# ServoConnector.net
KiCad netlist of a schematic drawn in Altium Designer
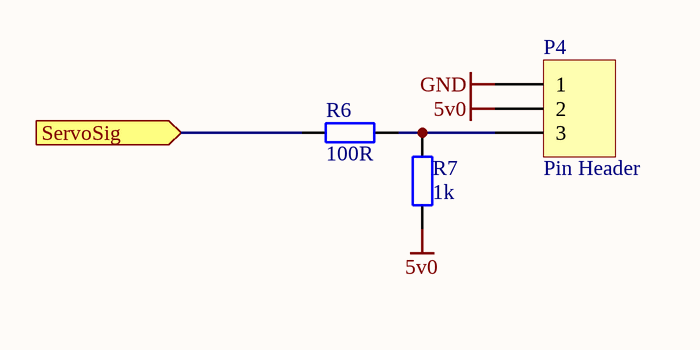
[diagram p0: ServoConnector.SchDoc]

(export (version "E")
  (design (tool "Eeschema 10.0.6"))
  (components
    (comp (ref "P4")
      (value "Pin Header")
      (footprint "PH1x3_2.54")
      (description "Con1x3")
      (fields (field (name "PART NUMBER") "PH1x3") (field (name "AUTHOR") "Willy Pietersz"))
      (libsource (lib "OurDb") (part "Con1x3"))
    )
    (comp (ref "R6")
      (value "100R")
      (footprint "R0805")
      (description "Resistor")
      (fields
        (field (name "POWER") "0.25W")
        (field (name "TOLERANCE") "0.05")
        (field (name "PUBLISHER") "Altium Limited")
        (field (name "AUTHOR") "Willy Pietersz")
      )
      (libsource (lib "OurDb") (part "RESISTOR"))
    )
    (comp (ref "R7")
      (value "1k")
      (footprint "R0805")
      (description "Resistor")
      (fields
        (field (name "PART NUMBER") "1K")
        (field (name "POWER") "0.25W")
        (field (name "PUBLISHER") "Altium Limited")
        (field (name "AUTHOR") "Willy Pietersz")
      )
      (libsource (lib "") (part "RESISTOR_1"))
    )
  )
  (nets
    (net (code "1") (name "/ServoSig") (class "Default")
      (node (ref "R6") (pin "2") (pinfunction "2_2") (pintype "passive"))
    )
    (net (code "2") (name "5v0") (class "Default")
      (node (ref "P4") (pin "2") (pinfunction "2_2") (pintype "passive"))
      (node (ref "R7") (pin "2") (pinfunction "2_2") (pintype "passive"))
    )
    (net (code "3") (name "GND") (class "Default")
      (node (ref "P4") (pin "1") (pinfunction "1_1") (pintype "passive"))
    )
    (net (code "4") (name "Net-(P4-Pad3)") (class "Default")
      (node (ref "P4") (pin "3") (pinfunction "3_3") (pintype "passive"))
      (node (ref "R6") (pin "1") (pinfunction "1_1") (pintype "passive"))
      (node (ref "R7") (pin "1") (pinfunction "1_1") (pintype "passive"))
    )
  )
)
